# rtc_accel.net
KiCad netlist of a schematic drawn in Altium Designer
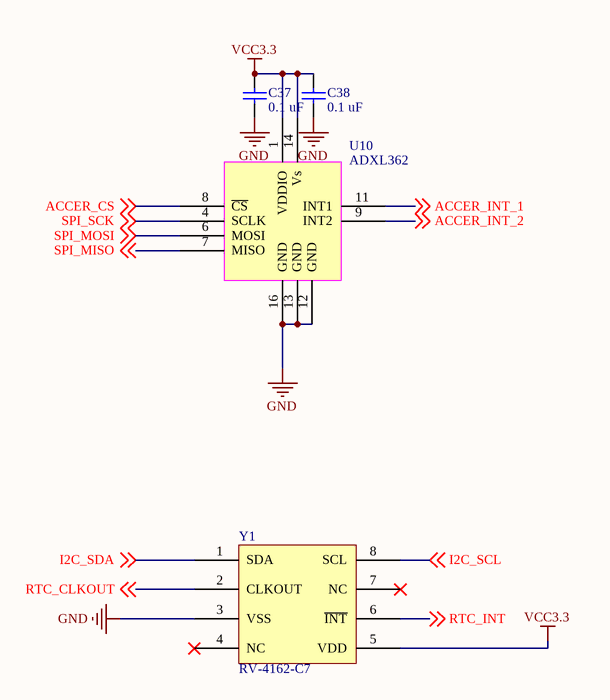
[diagram p0: rtc_accel.SchDoc]

(export (version "E")
  (design (tool "Eeschema 10.0.6"))
  (components
    (comp (ref "C37")
      (value "0.1 uF")
      (footprint "0402")
      (description "Ceramic capacitor, 0.1u, 0402 package")
      (fields (field (name "TOLERANCE") "10%") (field (name "Comment") "Ceramic capacitor"))
      (libsource (lib "rlc") (part "C_0.1u_0402_ceramic"))
    )
    (comp (ref "C38")
      (value "0.1 uF")
      (footprint "0402")
      (description "Ceramic capacitor, 0.1u, 0402 package")
      (fields (field (name "TOLERANCE") "10%") (field (name "Comment") "Ceramic capacitor"))
      (libsource (lib "rlc") (part "C_0.1u_0402_ceramic"))
    )
    (comp (ref "U10")
      (value "ADXL362")
      (footprint "LGA_CC-16-4")
      (description "Micropower, 3-Axis, ±2 g/±4 g/±8 g  Digital Output MEMS Accelerometer")
      (libsource (lib "opo") (part "ADXL362"))
    )
    (comp (ref "Y1")
      (value "RV-4162-C7")
      (footprint "RV4162")
      (description "Real Time Clock Module with I2C Bus")
      (libsource (lib "opo") (part "RV-4162-C7"))
    )
  )
  (nets
    (net (code "1") (name "ACCER_CS") (class "Default")
      (node (ref "U10") (pin "8") (pinfunction "~{CS}_8") (pintype "passive"))
    )
    (net (code "2") (name "ACCER_INT_1") (class "Default")
      (node (ref "U10") (pin "11") (pinfunction "INT1_11") (pintype "passive"))
    )
    (net (code "3") (name "ACCER_INT_2") (class "Default")
      (node (ref "U10") (pin "9") (pinfunction "INT2_9") (pintype "passive"))
    )
    (net (code "4") (name "GND") (class "Default")
      (node (ref "C37") (pin "2") (pintype "passive"))
      (node (ref "C38") (pin "2") (pintype "passive"))
      (node (ref "U10") (pin "12") (pinfunction "GND_12") (pintype "passive"))
      (node (ref "U10") (pin "13") (pinfunction "GND_13") (pintype "passive"))
      (node (ref "U10") (pin "16") (pinfunction "GND_16") (pintype "passive"))
      (node (ref "Y1") (pin "3") (pinfunction "VSS_3") (pintype "passive"))
    )
    (net (code "5") (name "I2C_SCL") (class "Default")
      (node (ref "Y1") (pin "8") (pinfunction "SCL_8") (pintype "passive"))
    )
    (net (code "6") (name "I2C_SDA") (class "Default")
      (node (ref "Y1") (pin "1") (pinfunction "SDA_1") (pintype "passive"))
    )
    (net (code "7") (name "RTC_CLKOUT") (class "Default")
      (node (ref "Y1") (pin "2") (pinfunction "CLKOUT_2") (pintype "passive"))
    )
    (net (code "8") (name "RTC_INT") (class "Default")
      (node (ref "Y1") (pin "6") (pinfunction "~{INT}_6") (pintype "passive"))
    )
    (net (code "9") (name "SPI_MISO") (class "Default")
      (node (ref "U10") (pin "7") (pinfunction "MISO_7") (pintype "passive"))
    )
    (net (code "10") (name "SPI_MOSI") (class "Default")
      (node (ref "U10") (pin "6") (pinfunction "MOSI_6") (pintype "passive"))
    )
    (net (code "11") (name "SPI_SCK") (class "Default")
      (node (ref "U10") (pin "4") (pinfunction "SCLK_4") (pintype "passive"))
    )
    (net (code "12") (name "VCC3.3") (class "Default")
      (node (ref "C37") (pin "1") (pintype "passive"))
      (node (ref "C38") (pin "1") (pintype "passive"))
      (node (ref "U10") (pin "1") (pinfunction "VDDIO_1") (pintype "passive"))
      (node (ref "U10") (pin "14") (pinfunction "Vs_14") (pintype "passive"))
      (node (ref "Y1") (pin "5") (pinfunction "VDD_5") (pintype "passive"))
    )
    (net (code "13") (name "unconnected-(Y1-NC-Pad4)") (class "Default")
      (node (ref "Y1") (pin "4") (pinfunction "NC_4") (pintype "passive+no_connect"))
    )
    (net (code "14") (name "unconnected-(Y1-NC-Pad7)") (class "Default")
      (node (ref "Y1") (pin "7") (pinfunction "NC_7") (pintype "passive+no_connect"))
    )
  )
)
